# GPS_Board_v0_1.net
KiCad netlist of a schematic drawn in EAGLE
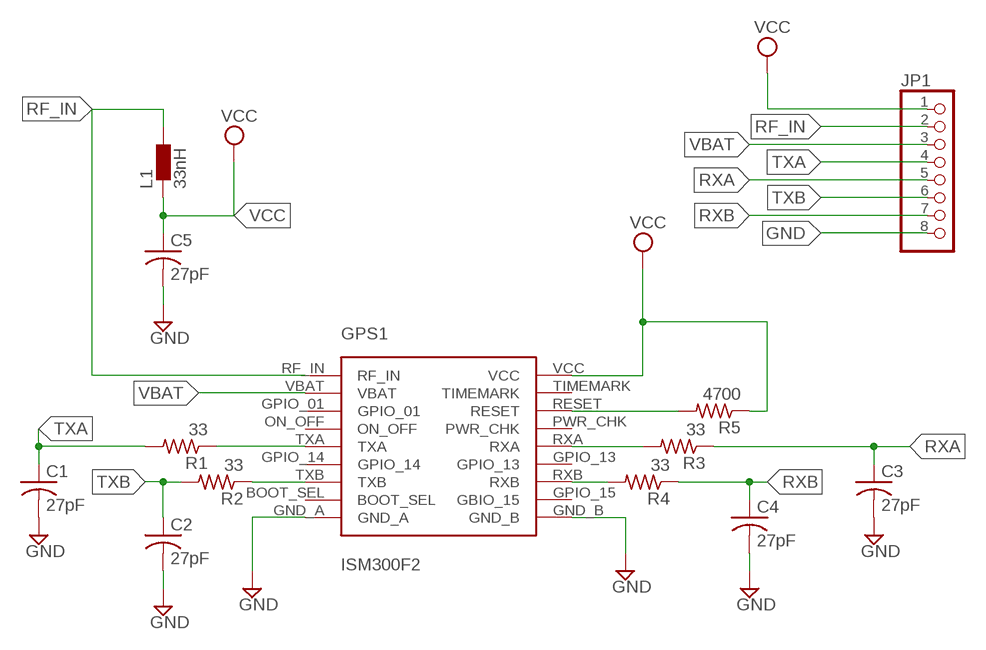
[diagram p0: schematic, sheet 1]

(export (version "E")
  (design (tool "Eeschema 10.0.6"))
  (components
    (comp (ref "C1")
      (value "27pF")
      (footprint "eagle-import:C0805K")
      (fields (field (name "MPN") "C0805C270J5GACTU"))
      (libsource (lib "eagle-import") (part "C-USC0805K"))
    )
    (comp (ref "C2")
      (value "27pF")
      (footprint "eagle-import:C0805K")
      (fields (field (name "MPN") "C0805C270J5GACTU"))
      (libsource (lib "eagle-import") (part "C-USC0805K"))
    )
    (comp (ref "C3")
      (value "27pF")
      (footprint "eagle-import:C0805K")
      (fields (field (name "MPN") "C0805C270J5GACTU"))
      (libsource (lib "eagle-import") (part "C-USC0805K"))
    )
    (comp (ref "C4")
      (value "27pF")
      (footprint "eagle-import:C0805K")
      (fields (field (name "MPN") "C0805C270J5GACTU"))
      (libsource (lib "eagle-import") (part "C-USC0805K"))
    )
    (comp (ref "C5")
      (value "27pF")
      (footprint "eagle-import:C0805K")
      (fields (field (name "MPN") "C0805C270J5GACTU"))
      (libsource (lib "eagle-import") (part "C-USC0805K"))
    )
    (comp (ref "GPS1")
      (value "ISM300F2")
      (footprint "eagle-import:ISM300F2")
      (libsource (lib "eagle-import") (part "ISM300F2"))
    )
    (comp (ref "JP1")
      (value "PINHD-1X8BIG")
      (footprint "eagle-import:1X08-BIG")
      (libsource (lib "eagle-import") (part "PINHD-1X8BIG"))
    )
    (comp (ref "L1")
      (value "33nH")
      (footprint "eagle-import:L4532P")
      (fields (field (name "MPN") "MCWL06KT33N"))
      (libsource (lib "eagle-import") (part "LL4532P"))
    )
    (comp (ref "R1")
      (value "33")
      (footprint "eagle-import:R0805")
      (fields (field (name "MF") "VISHAY/DALE") (field (name "MPN") "CRCW120633R2FKEA"))
      (libsource (lib "eagle-import") (part "R-US_R0805"))
    )
    (comp (ref "R2")
      (value "33")
      (footprint "eagle-import:R0805")
      (fields (field (name "MF") "VISHAY/DALE") (field (name "MPN") "CRCW120633R2FKEA"))
      (libsource (lib "eagle-import") (part "R-US_R0805"))
    )
    (comp (ref "R3")
      (value "33")
      (footprint "eagle-import:R0805")
      (fields (field (name "MF") "VISHAY/DALE") (field (name "MPN") "CRCW120633R2FKEA"))
      (libsource (lib "eagle-import") (part "R-US_R0805"))
    )
    (comp (ref "R4")
      (value "33")
      (footprint "eagle-import:R0805")
      (fields (field (name "MF") "VISHAY/DALE") (field (name "MPN") "CRCW120633R2FKEA"))
      (libsource (lib "eagle-import") (part "R-US_R0805"))
    )
    (comp (ref "R5")
      (value "4700")
      (footprint "eagle-import:R0805")
      (fields (field (name "MF") "VISHAY/DALE") (field (name "MPN") "CRCW12104K70FKEA"))
      (libsource (lib "eagle-import") (part "R-US_R0805"))
    )
  )
  (nets
    (net (code "1") (name "GND") (class "Default")
      (node (ref "C1") (pin "2") (pinfunction "2_2") (pintype "passive"))
      (node (ref "C2") (pin "2") (pinfunction "2_2") (pintype "passive"))
      (node (ref "C3") (pin "2") (pinfunction "2_2") (pintype "passive"))
      (node (ref "C4") (pin "2") (pinfunction "2_2") (pintype "passive"))
      (node (ref "C5") (pin "2") (pinfunction "2_2") (pintype "passive"))
      (node (ref "GPS1") (pin "GND_A") (pinfunction "GND_A_GND_A") (pintype "bidirectional"))
      (node (ref "GPS1") (pin "GND_B") (pinfunction "GND_B_GND_B") (pintype "bidirectional"))
      (node (ref "JP1") (pin "8") (pinfunction "8_8") (pintype "passive"))
    )
    (net (code "2") (name "Net-(GPS1-PadRESET)") (class "Default")
      (node (ref "GPS1") (pin "RESET") (pinfunction "RESET_RESET") (pintype "bidirectional"))
      (node (ref "R5") (pin "2") (pinfunction "2_2") (pintype "passive"))
    )
    (net (code "3") (name "Net-(GPS1-PadRXA)") (class "Default")
      (node (ref "GPS1") (pin "RXA") (pinfunction "RXA_RXA") (pintype "bidirectional"))
      (node (ref "R3") (pin "2") (pinfunction "2_2") (pintype "passive"))
    )
    (net (code "4") (name "Net-(GPS1-PadRXB)") (class "Default")
      (node (ref "GPS1") (pin "RXB") (pinfunction "RXB_RXB") (pintype "bidirectional"))
      (node (ref "R4") (pin "2") (pinfunction "2_2") (pintype "passive"))
    )
    (net (code "5") (name "Net-(GPS1-PadTXA)") (class "Default")
      (node (ref "GPS1") (pin "TXA") (pinfunction "TXA_TXA") (pintype "bidirectional"))
      (node (ref "R1") (pin "1") (pinfunction "1_1") (pintype "passive"))
    )
    (net (code "6") (name "Net-(GPS1-PadTXB)") (class "Default")
      (node (ref "GPS1") (pin "TXB") (pinfunction "TXB_TXB") (pintype "bidirectional"))
      (node (ref "R2") (pin "1") (pinfunction "1_1") (pintype "passive"))
    )
    (net (code "7") (name "RF_IN") (class "Default")
      (node (ref "GPS1") (pin "RF_IN") (pinfunction "RF_IN_RF_IN") (pintype "bidirectional"))
      (node (ref "JP1") (pin "2") (pinfunction "2_2") (pintype "passive"))
      (node (ref "L1") (pin "1") (pinfunction "1_1") (pintype "passive"))
    )
    (net (code "8") (name "RXA") (class "Default")
      (node (ref "C3") (pin "1") (pinfunction "1_1") (pintype "passive"))
      (node (ref "JP1") (pin "5") (pinfunction "5_5") (pintype "passive"))
      (node (ref "R3") (pin "1") (pinfunction "1_1") (pintype "passive"))
    )
    (net (code "9") (name "RXB") (class "Default")
      (node (ref "C4") (pin "1") (pinfunction "1_1") (pintype "passive"))
      (node (ref "JP1") (pin "7") (pinfunction "7_7") (pintype "passive"))
      (node (ref "R4") (pin "1") (pinfunction "1_1") (pintype "passive"))
    )
    (net (code "10") (name "TXA") (class "Default")
      (node (ref "C1") (pin "1") (pinfunction "1_1") (pintype "passive"))
      (node (ref "JP1") (pin "4") (pinfunction "4_4") (pintype "passive"))
      (node (ref "R1") (pin "2") (pinfunction "2_2") (pintype "passive"))
    )
    (net (code "11") (name "TXB") (class "Default")
      (node (ref "C2") (pin "1") (pinfunction "1_1") (pintype "passive"))
      (node (ref "JP1") (pin "6") (pinfunction "6_6") (pintype "passive"))
      (node (ref "R2") (pin "2") (pinfunction "2_2") (pintype "passive"))
    )
    (net (code "12") (name "VBAT") (class "Default")
      (node (ref "GPS1") (pin "VBAT") (pinfunction "VBAT_VBAT") (pintype "bidirectional"))
      (node (ref "JP1") (pin "3") (pinfunction "3_3") (pintype "passive"))
    )
    (net (code "13") (name "VCC") (class "Default")
      (node (ref "C5") (pin "1") (pinfunction "1_1") (pintype "passive"))
      (node (ref "GPS1") (pin "VCC") (pinfunction "VCC_VCC") (pintype "bidirectional"))
      (node (ref "JP1") (pin "1") (pinfunction "1_1") (pintype "passive"))
      (node (ref "L1") (pin "2") (pinfunction "2_2") (pintype "passive"))
      (node (ref "R5") (pin "1") (pinfunction "1_1") (pintype "passive"))
    )
    (net (code "14") (name "unconnected-(GPS1-GBIO_15-PadGPIO_15)") (class "Default")
      (node (ref "GPS1") (pin "GPIO_15") (pinfunction "GBIO_15_GPIO_15") (pintype "bidirectional"))
    )
    (net (code "15") (name "unconnected-(GPS1-PadBOOT_SEL)") (class "Default")
      (node (ref "GPS1") (pin "BOOT_SEL") (pinfunction "BOOT_SEL_BOOT_SEL") (pintype "bidirectional"))
    )
    (net (code "16") (name "unconnected-(GPS1-PadGPIO_01)") (class "Default")
      (node (ref "GPS1") (pin "GPIO_01") (pinfunction "GPIO_01_GPIO_01") (pintype "bidirectional"))
    )
    (net (code "17") (name "unconnected-(GPS1-PadGPIO_13)") (class "Default")
      (node (ref "GPS1") (pin "GPIO_13") (pinfunction "GPIO_13_GPIO_13") (pintype "bidirectional"))
    )
    (net (code "18") (name "unconnected-(GPS1-PadGPIO_14)") (class "Default")
      (node (ref "GPS1") (pin "GPIO_14") (pinfunction "GPIO_14_GPIO_14") (pintype "bidirectional"))
    )
    (net (code "19") (name "unconnected-(GPS1-PadON_OFF)") (class "Default")
      (node (ref "GPS1") (pin "ON_OFF") (pinfunction "ON_OFF_ON_OFF") (pintype "bidirectional"))
    )
    (net (code "20") (name "unconnected-(GPS1-PadPWR_CHK)") (class "Default")
      (node (ref "GPS1") (pin "PWR_CHK") (pinfunction "PWR_CHK_PWR_CHK") (pintype "bidirectional"))
    )
    (net (code "21") (name "unconnected-(GPS1-PadTIMEMARK)") (class "Default")
      (node (ref "GPS1") (pin "TIMEMARK") (pinfunction "TIMEMARK_TIMEMARK") (pintype "bidirectional"))
    )
  )
)
